# demeter_v23.net
KiCad netlist of a schematic drawn in EAGLE
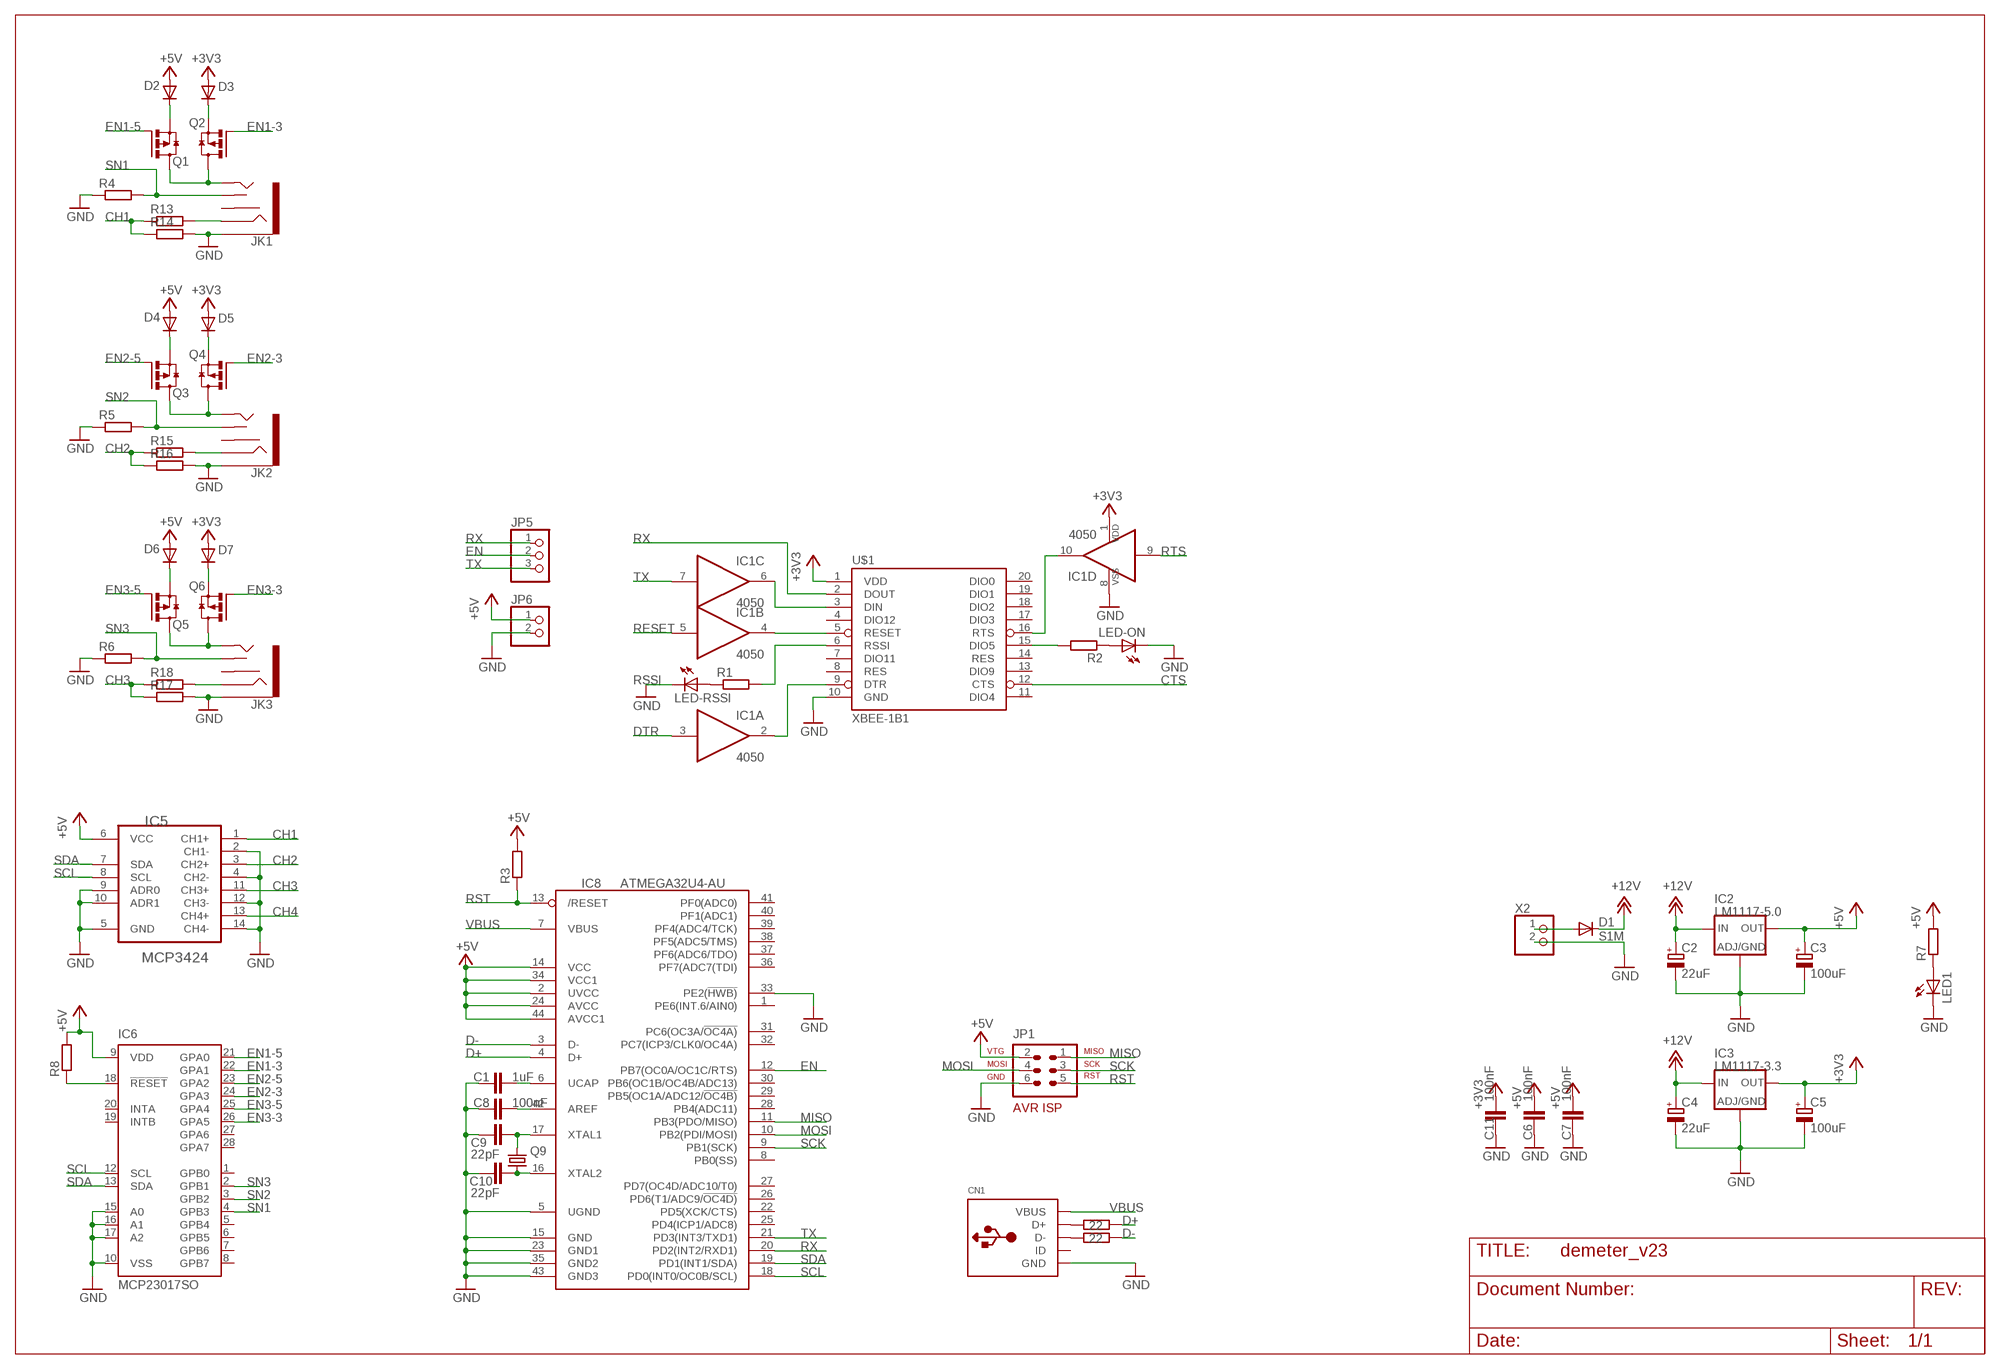
[diagram p0: schematic, sheet 1]

(export (version "E")
  (design (tool "Eeschema 10.0.6"))
  (components
    (comp (ref "C1")
      (value "1uF")
      (footprint "eagle-import:C0805K")
      (libsource (lib "eagle-import") (part "C-EUC0805K"))
    )
    (comp (ref "C2")
      (value "22uF")
      (footprint "eagle-import:PANASONIC_D")
      (libsource (lib "eagle-import") (part "CPOL-EUPD"))
    )
    (comp (ref "C3")
      (value "100uF")
      (footprint "eagle-import:PANASONIC_D")
      (libsource (lib "eagle-import") (part "CPOL-EUPD"))
    )
    (comp (ref "C4")
      (value "22uF")
      (footprint "eagle-import:PANASONIC_D")
      (libsource (lib "eagle-import") (part "CPOL-EUPD"))
    )
    (comp (ref "C5")
      (value "100uF")
      (footprint "eagle-import:PANASONIC_D")
      (libsource (lib "eagle-import") (part "CPOL-EUPD"))
    )
    (comp (ref "C6")
      (value "100nF")
      (footprint "eagle-import:C0805K")
      (libsource (lib "eagle-import") (part "C-EUC0805K"))
    )
    (comp (ref "C7")
      (value "100nF")
      (footprint "eagle-import:C0805K")
      (libsource (lib "eagle-import") (part "C-EUC0805K"))
    )
    (comp (ref "C8")
      (value "100nF")
      (footprint "eagle-import:C0805K")
      (libsource (lib "eagle-import") (part "C-EUC0805K"))
    )
    (comp (ref "C9")
      (value "22pF")
      (footprint "eagle-import:C0805K")
      (libsource (lib "eagle-import") (part "C-EUC0805K"))
    )
    (comp (ref "C10")
      (value "22pF")
      (footprint "eagle-import:C0805K")
      (libsource (lib "eagle-import") (part "C-EUC0805K"))
    )
    (comp (ref "C11")
      (value "100nF")
      (footprint "eagle-import:C0805K")
      (libsource (lib "eagle-import") (part "C-EUC0805K"))
    )
    (comp (ref "CN1")
      (value "USBMINIB")
      (footprint "eagle-import:USB-MINIB")
      (libsource (lib "eagle-import") (part "USBMINIB"))
    )
    (comp (ref "D1")
      (value "S1M")
      (footprint "eagle-import:DO-214AC")
      (libsource (lib "eagle-import") (part "S1M"))
    )
    (comp (ref "D2")
      (value "MBR0520")
      (footprint "eagle-import:SOD123")
      (libsource (lib "eagle-import") (part "MBR0520"))
    )
    (comp (ref "D3")
      (value "MBR0520")
      (footprint "eagle-import:SOD123")
      (libsource (lib "eagle-import") (part "MBR0520"))
    )
    (comp (ref "D4")
      (value "MBR0520")
      (footprint "eagle-import:SOD123")
      (libsource (lib "eagle-import") (part "MBR0520"))
    )
    (comp (ref "D5")
      (value "MBR0520")
      (footprint "eagle-import:SOD123")
      (libsource (lib "eagle-import") (part "MBR0520"))
    )
    (comp (ref "D6")
      (value "MBR0520")
      (footprint "eagle-import:SOD123")
      (libsource (lib "eagle-import") (part "MBR0520"))
    )
    (comp (ref "D7")
      (value "MBR0520")
      (footprint "eagle-import:SOD123")
      (libsource (lib "eagle-import") (part "MBR0520"))
    )
    (comp (ref "IC1")
      (value "4050")
      (footprint "eagle-import:SO16")
      (libsource (lib "eagle-import") (part "4050D"))
    )
    (comp (ref "IC2")
      (value "LM1117-5.0")
      (footprint "eagle-import:DPACK")
      (libsource (lib "eagle-import") (part "LM1117DT"))
    )
    (comp (ref "IC3")
      (value "LM1117-3.3")
      (footprint "eagle-import:DPACK")
      (libsource (lib "eagle-import") (part "LM1117DT"))
    )
    (comp (ref "IC5")
      (value "MCP3424")
      (footprint "eagle-import:SO14")
      (fields (field (name "MPN") "MCP3424-E/SL"))
      (libsource (lib "eagle-import") (part "MCP3424"))
    )
    (comp (ref "IC6")
      (value "MCP23017SO")
      (footprint "eagle-import:SO28W")
      (fields (field (name "MF") "MICROCHIP") (field (name "MPN") "MCP23017-E/SO"))
      (libsource (lib "eagle-import") (part "MCP23017SO"))
    )
    (comp (ref "IC8")
      (value "ATMEGA32U4-AU")
      (footprint "eagle-import:TQFP44")
      (libsource (lib "eagle-import") (part "ATMEGA32U4-AU"))
    )
    (comp (ref "JK1")
      (value "AUDIO-JACK2PTH")
      (footprint "eagle-import:AUDIO-JACK")
      (libsource (lib "eagle-import") (part "AUDIO-JACK2PTH"))
    )
    (comp (ref "JK2")
      (value "AUDIO-JACK2PTH")
      (footprint "eagle-import:AUDIO-JACK")
      (libsource (lib "eagle-import") (part "AUDIO-JACK2PTH"))
    )
    (comp (ref "JK3")
      (value "AUDIO-JACK2PTH")
      (footprint "eagle-import:AUDIO-JACK")
      (libsource (lib "eagle-import") (part "AUDIO-JACK2PTH"))
    )
    (comp (ref "JP1")
      (value "AVR-ISP-6")
      (footprint "eagle-import:AVR-ISP-6")
      (libsource (lib "eagle-import") (part "AVR-ISP-6"))
    )
    (comp (ref "JP5")
      (value "PINHD-1X3180")
      (footprint "eagle-import:1X03")
      (libsource (lib "eagle-import") (part "PINHD-1X3180"))
    )
    (comp (ref "JP6")
      (value "PINHD-1X2")
      (footprint "eagle-import:1X02")
      (libsource (lib "eagle-import") (part "PINHD-1X2"))
    )
    (comp (ref "LED-ON")
      (value "LED0805")
      (footprint "eagle-import:CHIP-LED0805")
      (libsource (lib "eagle-import") (part "LED0805"))
    )
    (comp (ref "LED-RSSI")
      (value "LED0805")
      (footprint "eagle-import:CHIP-LED0805")
      (libsource (lib "eagle-import") (part "LED0805"))
    )
    (comp (ref "LED1")
      (value "LED0805")
      (footprint "eagle-import:CHIP-LED0805")
      (libsource (lib "eagle-import") (part "LED0805"))
    )
    (comp (ref "Q1")
      (value "IRLML6402")
      (footprint "eagle-import:SOT23")
      (libsource (lib "eagle-import") (part "IRLML6402"))
    )
    (comp (ref "Q2")
      (value "IRLML6402")
      (footprint "eagle-import:SOT23")
      (libsource (lib "eagle-import") (part "IRLML6402"))
    )
    (comp (ref "Q3")
      (value "IRLML6402")
      (footprint "eagle-import:SOT23")
      (libsource (lib "eagle-import") (part "IRLML6402"))
    )
    (comp (ref "Q4")
      (value "IRLML6402")
      (footprint "eagle-import:SOT23")
      (libsource (lib "eagle-import") (part "IRLML6402"))
    )
    (comp (ref "Q5")
      (value "IRLML6402")
      (footprint "eagle-import:SOT23")
      (libsource (lib "eagle-import") (part "IRLML6402"))
    )
    (comp (ref "Q6")
      (value "IRLML6402")
      (footprint "eagle-import:SOT23")
      (libsource (lib "eagle-import") (part "IRLML6402"))
    )
    (comp (ref "Q9")
      (value "CRYSTALHC49UP")
      (footprint "eagle-import:HC49UP")
      (libsource (lib "eagle-import") (part "CRYSTALHC49UP"))
    )
    (comp (ref "R1")
      (value "R-EU_R0805")
      (footprint "eagle-import:R0805")
      (libsource (lib "eagle-import") (part "R-EU_R0805"))
    )
    (comp (ref "R2")
      (value "R-EU_R0805")
      (footprint "eagle-import:R0805")
      (libsource (lib "eagle-import") (part "R-EU_R0805"))
    )
    (comp (ref "R3")
      (value "R-EU_R0805")
      (footprint "eagle-import:R0805")
      (libsource (lib "eagle-import") (part "R-EU_R0805"))
    )
    (comp (ref "R4")
      (value "R-EU_R0805")
      (footprint "eagle-import:R0805")
      (libsource (lib "eagle-import") (part "R-EU_R0805"))
    )
    (comp (ref "R5")
      (value "R-EU_R0805")
      (footprint "eagle-import:R0805")
      (libsource (lib "eagle-import") (part "R-EU_R0805"))
    )
    (comp (ref "R6")
      (value "R-EU_R0805")
      (footprint "eagle-import:R0805")
      (libsource (lib "eagle-import") (part "R-EU_R0805"))
    )
    (comp (ref "R7")
      (value "R-EU_R0805")
      (footprint "eagle-import:R0805")
      (libsource (lib "eagle-import") (part "R-EU_R0805"))
    )
    (comp (ref "R8")
      (value "R-EU_R0805")
      (footprint "eagle-import:R0805")
      (libsource (lib "eagle-import") (part "R-EU_R0805"))
    )
    (comp (ref "R9")
      (value "22")
      (footprint "eagle-import:R0805")
      (libsource (lib "eagle-import") (part "R-EU_R0805"))
    )
    (comp (ref "R10")
      (value "22")
      (footprint "eagle-import:R0805")
      (libsource (lib "eagle-import") (part "R-EU_R0805"))
    )
    (comp (ref "R13")
      (value "R-EU_R0805")
      (footprint "eagle-import:R0805")
      (libsource (lib "eagle-import") (part "R-EU_R0805"))
    )
    (comp (ref "R14")
      (value "R-EU_R0805")
      (footprint "eagle-import:R0805")
      (libsource (lib "eagle-import") (part "R-EU_R0805"))
    )
    (comp (ref "R15")
      (value "R-EU_R0805")
      (footprint "eagle-import:R0805")
      (libsource (lib "eagle-import") (part "R-EU_R0805"))
    )
    (comp (ref "R16")
      (value "R-EU_R0805")
      (footprint "eagle-import:R0805")
      (libsource (lib "eagle-import") (part "R-EU_R0805"))
    )
    (comp (ref "R17")
      (value "R-EU_R0805")
      (footprint "eagle-import:R0805")
      (libsource (lib "eagle-import") (part "R-EU_R0805"))
    )
    (comp (ref "R18")
      (value "R-EU_R0805")
      (footprint "eagle-import:R0805")
      (libsource (lib "eagle-import") (part "R-EU_R0805"))
    )
    (comp (ref "U$1")
      (value "XBEE-1B1")
      (footprint "eagle-import:XBEE-1")
      (libsource (lib "eagle-import") (part "XBEE-1B1"))
    )
    (comp (ref "X2")
      (value "W237-102")
      (footprint "eagle-import:W237-102")
      (libsource (lib "eagle-import") (part "W237-102"))
    )
  )
  (nets
    (net (code "1") (name "+3V3") (class "Default")
      (node (ref "C11") (pin "1") (pinfunction "1_1") (pintype "passive"))
      (node (ref "C5") (pin "+") (pinfunction "+_+") (pintype "passive"))
      (node (ref "D3") (pin "A") (pinfunction "A_A") (pintype "passive"))
      (node (ref "D5") (pin "A") (pinfunction "A_A") (pintype "passive"))
      (node (ref "D7") (pin "A") (pinfunction "A_A") (pintype "passive"))
      (node (ref "IC1") (pin "1") (pinfunction "VDD_1") (pintype "power_in"))
      (node (ref "IC3") (pin "4") (pinfunction "OUT_4") (pintype "passive"))
      (node (ref "U$1") (pin "1") (pinfunction "VDD_1") (pintype "power_in"))
    )
    (net (code "2") (name "+5V") (class "Default")
      (node (ref "C3") (pin "+") (pinfunction "+_+") (pintype "passive"))
      (node (ref "C6") (pin "1") (pinfunction "1_1") (pintype "passive"))
      (node (ref "C7") (pin "1") (pinfunction "1_1") (pintype "passive"))
      (node (ref "D2") (pin "A") (pinfunction "A_A") (pintype "passive"))
      (node (ref "D4") (pin "A") (pinfunction "A_A") (pintype "passive"))
      (node (ref "D6") (pin "A") (pinfunction "A_A") (pintype "passive"))
      (node (ref "IC2") (pin "4") (pinfunction "OUT_4") (pintype "passive"))
      (node (ref "IC5") (pin "6") (pinfunction "VCC_6") (pintype "power_in"))
      (node (ref "IC6") (pin "9") (pinfunction "VDD_9") (pintype "power_in"))
      (node (ref "IC8") (pin "14") (pinfunction "VCC_14") (pintype "bidirectional"))
      (node (ref "IC8") (pin "2") (pinfunction "UVCC_2") (pintype "bidirectional"))
      (node (ref "IC8") (pin "24") (pinfunction "AVCC_24") (pintype "bidirectional"))
      (node (ref "IC8") (pin "34") (pinfunction "VCC1_34") (pintype "bidirectional"))
      (node (ref "IC8") (pin "44") (pinfunction "AVCC1_44") (pintype "bidirectional"))
      (node (ref "JP1") (pin "2") (pinfunction "VTG_2") (pintype "passive"))
      (node (ref "JP6") (pin "1") (pinfunction "1_1") (pintype "passive"))
      (node (ref "R3") (pin "2") (pinfunction "2_2") (pintype "passive"))
      (node (ref "R7") (pin "2") (pinfunction "2_2") (pintype "passive"))
      (node (ref "R8") (pin "2") (pinfunction "2_2") (pintype "passive"))
    )
    (net (code "3") (name "+12V") (class "Default")
      (node (ref "C2") (pin "+") (pinfunction "+_+") (pintype "passive"))
      (node (ref "C4") (pin "+") (pinfunction "+_+") (pintype "passive"))
      (node (ref "D1") (pin "C") (pinfunction "C_C") (pintype "passive"))
      (node (ref "IC2") (pin "3") (pinfunction "IN_3") (pintype "input"))
      (node (ref "IC3") (pin "3") (pinfunction "IN_3") (pintype "input"))
    )
    (net (code "4") (name "/CH1") (class "Default")
      (node (ref "IC5") (pin "1") (pinfunction "CH1+_1") (pintype "input"))
      (node (ref "R13") (pin "1") (pinfunction "1_1") (pintype "passive"))
      (node (ref "R14") (pin "1") (pinfunction "1_1") (pintype "passive"))
    )
    (net (code "5") (name "/CH2") (class "Default")
      (node (ref "IC5") (pin "3") (pinfunction "CH2+_3") (pintype "input"))
      (node (ref "R15") (pin "1") (pinfunction "1_1") (pintype "passive"))
      (node (ref "R16") (pin "1") (pinfunction "1_1") (pintype "passive"))
    )
    (net (code "6") (name "/CH3") (class "Default")
      (node (ref "IC5") (pin "11") (pinfunction "CH3+_11") (pintype "input"))
      (node (ref "R17") (pin "1") (pinfunction "1_1") (pintype "passive"))
      (node (ref "R18") (pin "1") (pinfunction "1_1") (pintype "passive"))
    )
    (net (code "7") (name "/CH4") (class "Default")
      (node (ref "IC5") (pin "13") (pinfunction "CH4+_13") (pintype "input"))
    )
    (net (code "8") (name "/CTS") (class "Default")
      (node (ref "U$1") (pin "12") (pinfunction "CTS_12") (pintype "output"))
    )
    (net (code "9") (name "/D+") (class "Default")
      (node (ref "IC8") (pin "4") (pinfunction "D+_4") (pintype "bidirectional"))
      (node (ref "R9") (pin "1") (pinfunction "1_1") (pintype "passive"))
    )
    (net (code "10") (name "/D-") (class "Default")
      (node (ref "IC8") (pin "3") (pinfunction "D-_3") (pintype "bidirectional"))
      (node (ref "R10") (pin "1") (pinfunction "1_1") (pintype "passive"))
    )
    (net (code "11") (name "/DTR") (class "Default")
      (node (ref "IC1") (pin "3") (pinfunction "I_3") (pintype "input"))
    )
    (net (code "12") (name "/EN") (class "Default")
      (node (ref "IC8") (pin "12") (pinfunction "PB7(OC0A/OC1C/RTS)_12") (pintype "bidirectional"))
      (node (ref "JP5") (pin "2") (pinfunction "2_2") (pintype "passive"))
    )
    (net (code "13") (name "/EN1-3") (class "Default")
      (node (ref "IC6") (pin "22") (pinfunction "GPA1_22") (pintype "bidirectional"))
      (node (ref "Q2") (pin "1") (pinfunction "G_1") (pintype "passive"))
    )
    (net (code "14") (name "/EN1-5") (class "Default")
      (node (ref "IC6") (pin "21") (pinfunction "GPA0_21") (pintype "bidirectional"))
      (node (ref "Q1") (pin "1") (pinfunction "G_1") (pintype "passive"))
    )
    (net (code "15") (name "/EN2-3") (class "Default")
      (node (ref "IC6") (pin "24") (pinfunction "GPA3_24") (pintype "bidirectional"))
      (node (ref "Q4") (pin "1") (pinfunction "G_1") (pintype "passive"))
    )
    (net (code "16") (name "/EN2-5") (class "Default")
      (node (ref "IC6") (pin "23") (pinfunction "GPA2_23") (pintype "bidirectional"))
      (node (ref "Q3") (pin "1") (pinfunction "G_1") (pintype "passive"))
    )
    (net (code "17") (name "/EN3-3") (class "Default")
      (node (ref "IC6") (pin "26") (pinfunction "GPA5_26") (pintype "bidirectional"))
      (node (ref "Q6") (pin "1") (pinfunction "G_1") (pintype "passive"))
    )
    (net (code "18") (name "/EN3-5") (class "Default")
      (node (ref "IC6") (pin "25") (pinfunction "GPA4_25") (pintype "bidirectional"))
      (node (ref "Q5") (pin "1") (pinfunction "G_1") (pintype "passive"))
    )
    (net (code "19") (name "/MISO") (class "Default")
      (node (ref "IC8") (pin "11") (pinfunction "PB3(PDO/MISO)_11") (pintype "bidirectional"))
      (node (ref "JP1") (pin "1") (pinfunction "MISO_1") (pintype "passive"))
    )
    (net (code "20") (name "/MOSI") (class "Default")
      (node (ref "IC8") (pin "10") (pinfunction "PB2(PDI/MOSI)_10") (pintype "bidirectional"))
      (node (ref "JP1") (pin "4") (pinfunction "MOSI_4") (pintype "passive"))
    )
    (net (code "21") (name "/RESET") (class "Default")
      (node (ref "IC1") (pin "5") (pinfunction "I_5") (pintype "input"))
    )
    (net (code "22") (name "/RSSI") (class "Default")
      (node (ref "R1") (pin "2") (pinfunction "2_2") (pintype "passive"))
      (node (ref "U$1") (pin "6") (pinfunction "RSSI_6") (pintype "bidirectional"))
    )
    (net (code "23") (name "/RST") (class "Default")
      (node (ref "IC8") (pin "13") (pinfunction "/RESET_13") (pintype "bidirectional"))
      (node (ref "JP1") (pin "5") (pinfunction "RST_5") (pintype "passive"))
      (node (ref "R3") (pin "1") (pinfunction "1_1") (pintype "passive"))
    )
    (net (code "24") (name "/RTS") (class "Default")
      (node (ref "IC1") (pin "9") (pinfunction "I_9") (pintype "input"))
    )
    (net (code "25") (name "/RX") (class "Default")
      (node (ref "IC8") (pin "20") (pinfunction "PD2(INT2/RXD1)_20") (pintype "bidirectional"))
      (node (ref "JP5") (pin "1") (pinfunction "1_1") (pintype "passive"))
      (node (ref "U$1") (pin "2") (pinfunction "DOUT_2") (pintype "output"))
    )
    (net (code "26") (name "/SCK") (class "Default")
      (node (ref "IC8") (pin "9") (pinfunction "PB1(SCK)_9") (pintype "bidirectional"))
      (node (ref "JP1") (pin "3") (pinfunction "SCK_3") (pintype "passive"))
    )
    (net (code "27") (name "/SCL") (class "Default")
      (node (ref "IC5") (pin "8") (pinfunction "SCL_8") (pintype "input"))
      (node (ref "IC6") (pin "12") (pinfunction "SCL_12") (pintype "input"))
      (node (ref "IC8") (pin "18") (pinfunction "PD0(INT0/OC0B/SCL)_18") (pintype "bidirectional"))
    )
    (net (code "28") (name "/SDA") (class "Default")
      (node (ref "IC5") (pin "7") (pinfunction "SDA_7") (pintype "bidirectional"))
      (node (ref "IC6") (pin "13") (pinfunction "SDA_13") (pintype "bidirectional"))
      (node (ref "IC8") (pin "19") (pinfunction "PD1(INT1/SDA)_19") (pintype "bidirectional"))
    )
    (net (code "29") (name "/SN1") (class "Default")
      (node (ref "IC6") (pin "4") (pinfunction "GPB3_4") (pintype "bidirectional"))
      (node (ref "JK1") (pin "TSH") (pinfunction "TSH_TSH") (pintype "bidirectional"))
      (node (ref "R4") (pin "2") (pinfunction "2_2") (pintype "passive"))
    )
    (net (code "30") (name "/SN2") (class "Default")
      (node (ref "IC6") (pin "3") (pinfunction "GPB2_3") (pintype "bidirectional"))
      (node (ref "JK2") (pin "TSH") (pinfunction "TSH_TSH") (pintype "bidirectional"))
      (node (ref "R5") (pin "2") (pinfunction "2_2") (pintype "passive"))
    )
    (net (code "31") (name "/SN3") (class "Default")
      (node (ref "IC6") (pin "2") (pinfunction "GPB1_2") (pintype "bidirectional"))
      (node (ref "JK3") (pin "TSH") (pinfunction "TSH_TSH") (pintype "bidirectional"))
      (node (ref "R6") (pin "2") (pinfunction "2_2") (pintype "passive"))
    )
    (net (code "32") (name "/TX") (class "Default")
      (node (ref "IC1") (pin "7") (pinfunction "I_7") (pintype "input"))
      (node (ref "IC8") (pin "21") (pinfunction "PD3(INT3/TXD1)_21") (pintype "bidirectional"))
      (node (ref "JP5") (pin "3") (pinfunction "3_3") (pintype "passive"))
    )
    (net (code "33") (name "/VBUS") (class "Default")
      (node (ref "CN1") (pin "VBUS") (pinfunction "VBUS_VBUS") (pintype "power_in"))
      (node (ref "IC8") (pin "7") (pinfunction "VBUS_7") (pintype "bidirectional"))
    )
    (net (code "34") (name "GND") (class "Default")
      (node (ref "C1") (pin "2") (pinfunction "2_2") (pintype "passive"))
      (node (ref "C10") (pin "2") (pinfunction "2_2") (pintype "passive"))
      (node (ref "C11") (pin "2") (pinfunction "2_2") (pintype "passive"))
      (node (ref "C2") (pin "-") (pinfunction "-_-") (pintype "passive"))
      (node (ref "C3") (pin "-") (pinfunction "-_-") (pintype "passive"))
      (node (ref "C4") (pin "-") (pinfunction "-_-") (pintype "passive"))
      (node (ref "C5") (pin "-") (pinfunction "-_-") (pintype "passive"))
      (node (ref "C6") (pin "2") (pinfunction "2_2") (pintype "passive"))
      (node (ref "C7") (pin "2") (pinfunction "2_2") (pintype "passive"))
      (node (ref "C8") (pin "2") (pinfunction "2_2") (pintype "passive"))
      (node (ref "C9") (pin "2") (pinfunction "2_2") (pintype "passive"))
      (node (ref "CN1") (pin "GND") (pinfunction "GND_GND") (pintype "power_in"))
      (node (ref "IC1") (pin "8") (pinfunction "VSS_8") (pintype "power_in"))
      (node (ref "IC2") (pin "1") (pinfunction "ADJ_1") (pintype "input"))
      (node (ref "IC3") (pin "1") (pinfunction "ADJ_1") (pintype "input"))
      (node (ref "IC5") (pin "10") (pinfunction "ADR1_10") (pintype "input"))
      (node (ref "IC5") (pin "12") (pinfunction "CH3-_12") (pintype "input"))
      (node (ref "IC5") (pin "14") (pinfunction "CH4-_14") (pintype "input"))
      (node (ref "IC5") (pin "2") (pinfunction "CH1-_2") (pintype "input"))
      (node (ref "IC5") (pin "4") (pinfunction "CH2-_4") (pintype "input"))
      (node (ref "IC5") (pin "5") (pinfunction "GND_5") (pintype "power_in"))
      (node (ref "IC5") (pin "9") (pinfunction "ADR0_9") (pintype "input"))
      (node (ref "IC6") (pin "10") (pinfunction "VSS_10") (pintype "power_in"))
      (node (ref "IC6") (pin "15") (pinfunction "A0_15") (pintype "input"))
      (node (ref "IC6") (pin "16") (pinfunction "A1_16") (pintype "input"))
      (node (ref "IC6") (pin "17") (pinfunction "A2_17") (pintype "input"))
      (node (ref "IC8") (pin "15") (pinfunction "GND_15") (pintype "bidirectional"))
      (node (ref "IC8") (pin "23") (pinfunction "GND1_23") (pintype "bidirectional"))
      (node (ref "IC8") (pin "33") (pinfunction "PE2(~{HWB})_33") (pintype "bidirectional"))
      (node (ref "IC8") (pin "35") (pinfunction "GND2_35") (pintype "bidirectional"))
      (node (ref "IC8") (pin "43") (pinfunction "GND3_43") (pintype "bidirectional"))
      (node (ref "IC8") (pin "5") (pinfunction "UGND_5") (pintype "bidirectional"))
      (node (ref "JK1") (pin "SLEEVE") (pinfunction "SLEEVE_SLEEVE") (pintype "bidirectional"))
      (node (ref "JK2") (pin "SLEEVE") (pinfunction "SLEEVE_SLEEVE") (pintype "bidirectional"))
      (node (ref "JK3") (pin "SLEEVE") (pinfunction "SLEEVE_SLEEVE") (pintype "bidirectional"))
      (node (ref "JP1") (pin "6") (pinfunction "GND_6") (pintype "passive"))
      (node (ref "JP6") (pin "2") (pinfunction "2_2") (pintype "passive"))
      (node (ref "LED-ON") (pin "C") (pinfunction "C_C") (pintype "passive"))
      (node (ref "LED-RSSI") (pin "C") (pinfunction "C_C") (pintype "passive"))
      (node (ref "LED1") (pin "C") (pinfunction "C_C") (pintype "passive"))
      (node (ref "R14") (pin "2") (pinfunction "2_2") (pintype "passive"))
      (node (ref "R16") (pin "2") (pinfunction "2_2") (pintype "passive"))
      (node (ref "R17") (pin "2") (pinfunction "2_2") (pintype "passive"))
      (node (ref "R4") (pin "1") (pinfunction "1_1") (pintype "passive"))
      (node (ref "R5") (pin "1") (pinfunction "1_1") (pintype "passive"))
      (node (ref "R6") (pin "1") (pinfunction "1_1") (pintype "passive"))
      (node (ref "U$1") (pin "10") (pinfunction "GND_10") (pintype "power_in"))
      (node (ref "X2") (pin "2") (pinfunction "2_2") (pintype "passive"))
    )
    (net (code "35") (name "Net-(CN1-PadD+)") (class "Default")
      (node (ref "CN1") (pin "D+") (pinfunction "D+_D+") (pintype "bidirectional"))
      (node (ref "R9") (pin "2") (pinfunction "2_2") (pintype "passive"))
    )
    (net (code "36") (name "Net-(CN1-PadD-)") (class "Default")
      (node (ref "CN1") (pin "D-") (pinfunction "D-_D-") (pintype "bidirectional"))
      (node (ref "R10") (pin "2") (pinfunction "2_2") (pintype "passive"))
    )
    (net (code "37") (name "Net-(D1-PadA)") (class "Default")
      (node (ref "D1") (pin "A") (pinfunction "A_A") (pintype "passive"))
      (node (ref "X2") (pin "1") (pinfunction "1_1") (pintype "passive"))
    )
    (net (code "38") (name "Net-(IC1A-O)") (class "Default")
      (node (ref "IC1") (pin "2") (pinfunction "O_2") (pintype "output"))
      (node (ref "U$1") (pin "9") (pinfunction "DTR_9") (pintype "bidirectional"))
    )
    (net (code "39") (name "Net-(IC1B-O)") (class "Default")
      (node (ref "IC1") (pin "4") (pinfunction "O_4") (pintype "output"))
      (node (ref "U$1") (pin "5") (pinfunction "RESET_5") (pintype "input"))
    )
    (net (code "40") (name "Net-(IC1C-O)") (class "Default")
      (node (ref "IC1") (pin "6") (pinfunction "O_6") (pintype "output"))
      (node (ref "U$1") (pin "3") (pinfunction "DIN_3") (pintype "input"))
    )
    (net (code "41") (name "Net-(IC1D-O)") (class "Default")
      (node (ref "IC1") (pin "10") (pinfunction "O_10") (pintype "output"))
      (node (ref "U$1") (pin "16") (pinfunction "RTS_16") (pintype "input"))
    )
    (net (code "42") (name "Net-(IC6-~{RESET})") (class "Default")
      (node (ref "IC6") (pin "18") (pinfunction "~{RESET}_18") (pintype "input"))
      (node (ref "R8") (pin "1") (pinfunction "1_1") (pintype "passive"))
    )
    (net (code "43") (name "Net-(IC8-AREF)") (class "Default")
      (node (ref "C8") (pin "1") (pinfunction "1_1") (pintype "passive"))
      (node (ref "IC8") (pin "42") (pinfunction "AREF_42") (pintype "bidirectional"))
    )
    (net (code "44") (name "Net-(IC8-UCAP)") (class "Default")
      (node (ref "C1") (pin "1") (pinfunction "1_1") (pintype "passive"))
      (node (ref "IC8") (pin "6") (pinfunction "UCAP_6") (pintype "bidirectional"))
    )
    (net (code "45") (name "Net-(IC8-XTAL1)") (class "Default")
      (node (ref "C9") (pin "1") (pinfunction "1_1") (pintype "passive"))
      (node (ref "IC8") (pin "17") (pinfunction "XTAL1_17") (pintype "bidirectional"))
      (node (ref "Q9") (pin "2") (pinfunction "2_2") (pintype "passive"))
    )
    (net (code "46") (name "Net-(IC8-XTAL2)") (class "Default")
      (node (ref "C10") (pin "1") (pinfunction "1_1") (pintype "passive"))
      (node (ref "IC8") (pin "16") (pinfunction "XTAL2_16") (pintype "bidirectional"))
      (node (ref "Q9") (pin "1") (pinfunction "1_1") (pintype "passive"))
    )
    (net (code "47") (name "Net-(JK1-PadRING)") (class "Default")
      (node (ref "JK1") (pin "RING") (pinfunction "RING_RING") (pintype "bidirectional"))
      (node (ref "R13") (pin "2") (pinfunction "2_2") (pintype "passive"))
    )
    (net (code "48") (name "Net-(JK2-PadRING)") (class "Default")
      (node (ref "JK2") (pin "RING") (pinfunction "RING_RING") (pintype "bidirectional"))
      (node (ref "R15") (pin "2") (pinfunction "2_2") (pintype "passive"))
    )
    (net (code "49") (name "Net-(JK3-PadRING)") (class "Default")
      (node (ref "JK3") (pin "RING") (pinfunction "RING_RING") (pintype "bidirectional"))
      (node (ref "R18") (pin "2") (pinfunction "2_2") (pintype "passive"))
    )
    (net (code "50") (name "Net-(LED-ON-PadA)") (class "Default")
      (node (ref "LED-ON") (pin "A") (pinfunction "A_A") (pintype "passive"))
      (node (ref "R2") (pin "1") (pinfunction "1_1") (pintype "passive"))
    )
    (net (code "51") (name "Net-(LED-RSSI-PadA)") (class "Default")
      (node (ref "LED-RSSI") (pin "A") (pinfunction "A_A") (pintype "passive"))
      (node (ref "R1") (pin "1") (pinfunction "1_1") (pintype "passive"))
    )
    (net (code "52") (name "Net-(LED1-PadA)") (class "Default")
      (node (ref "LED1") (pin "A") (pinfunction "A_A") (pintype "passive"))
      (node (ref "R7") (pin "1") (pinfunction "1_1") (pintype "passive"))
    )
    (net (code "53") (name "Net-(Q1-D)") (class "Default")
      (node (ref "JK1") (pin "TIP") (pinfunction "TIP_TIP") (pintype "bidirectional"))
      (node (ref "Q1") (pin "3") (pinfunction "D_3") (pintype "passive"))
      (node (ref "Q2") (pin "3") (pinfunction "D_3") (pintype "passive"))
    )
    (net (code "54") (name "Net-(Q1-S)") (class "Default")
      (node (ref "D2") (pin "C") (pinfunction "C_C") (pintype "passive"))
      (node (ref "Q1") (pin "2") (pinfunction "S_2") (pintype "passive"))
    )
    (net (code "55") (name "Net-(Q2-S)") (class "Default")
      (node (ref "D3") (pin "C") (pinfunction "C_C") (pintype "passive"))
      (node (ref "Q2") (pin "2") (pinfunction "S_2") (pintype "passive"))
    )
    (net (code "56") (name "Net-(Q3-D)") (class "Default")
      (node (ref "JK2") (pin "TIP") (pinfunction "TIP_TIP") (pintype "bidirectional"))
      (node (ref "Q3") (pin "3") (pinfunction "D_3") (pintype "passive"))
      (node (ref "Q4") (pin "3") (pinfunction "D_3") (pintype "passive"))
    )
    (net (code "57") (name "Net-(Q3-S)") (class "Default")
      (node (ref "D4") (pin "C") (pinfunction "C_C") (pintype "passive"))
      (node (ref "Q3") (pin "2") (pinfunction "S_2") (pintype "passive"))
    )
    (net (code "58") (name "Net-(Q4-S)") (class "Default")
      (node (ref "D5") (pin "C") (pinfunction "C_C") (pintype "passive"))
      (node (ref "Q4") (pin "2") (pinfunction "S_2") (pintype "passive"))
    )
    (net (code "59") (name "Net-(Q5-D)") (class "Default")
      (node (ref "JK3") (pin "TIP") (pinfunction "TIP_TIP") (pintype "bidirectional"))
      (node (ref "Q5") (pin "3") (pinfunction "D_3") (pintype "passive"))
      (node (ref "Q6") (pin "3") (pinfunction "D_3") (pintype "passive"))
    )
    (net (code "60") (name "Net-(Q5-S)") (class "Default")
      (node (ref "D6") (pin "C") (pinfunction "C_C") (pintype "passive"))
      (node (ref "Q5") (pin "2") (pinfunction "S_2") (pintype "passive"))
    )
    (net (code "61") (name "Net-(Q6-S)") (class "Default")
      (node (ref "D7") (pin "C") (pinfunction "C_C") (pintype "passive"))
      (node (ref "Q6") (pin "2") (pinfunction "S_2") (pintype "passive"))
    )
    (net (code "62") (name "Net-(U$1-DIO5)") (class "Default")
      (node (ref "R2") (pin "2") (pinfunction "2_2") (pintype "passive"))
      (node (ref "U$1") (pin "15") (pinfunction "DIO5_15") (pintype "bidirectional"))
    )
    (net (code "63") (name "unconnected-(CN1-PadID)") (class "Default")
      (node (ref "CN1") (pin "ID") (pinfunction "ID_ID") (pintype "bidirectional"))
    )
    (net (code "64") (name "unconnected-(IC6-GPA6-Pad27)") (class "Default")
      (node (ref "IC6") (pin "27") (pinfunction "GPA6_27") (pintype "bidirectional"))
    )
    (net (code "65") (name "unconnected-(IC6-GPA7-Pad28)") (class "Default")
      (node (ref "IC6") (pin "28") (pinfunction "GPA7_28") (pintype "bidirectional"))
    )
    (net (code "66") (name "unconnected-(IC6-GPB0-Pad1)") (class "Default")
      (node (ref "IC6") (pin "1") (pinfunction "GPB0_1") (pintype "bidirectional"))
    )
    (net (code "67") (name "unconnected-(IC6-GPB4-Pad5)") (class "Default")
      (node (ref "IC6") (pin "5") (pinfunction "GPB4_5") (pintype "bidirectional"))
    )
    (net (code "68") (name "unconnected-(IC6-GPB5-Pad6)") (class "Default")
      (node (ref "IC6") (pin "6") (pinfunction "GPB5_6") (pintype "bidirectional"))
    )
    (net (code "69") (name "unconnected-(IC6-GPB6-Pad7)") (class "Default")
      (node (ref "IC6") (pin "7") (pinfunction "GPB6_7") (pintype "bidirectional"))
    )
    (net (code "70") (name "unconnected-(IC6-GPB7-Pad8)") (class "Default")
      (node (ref "IC6") (pin "8") (pinfunction "GPB7_8") (pintype "bidirectional"))
    )
    (net (code "71") (name "unconnected-(IC6-INTA-Pad20)") (class "Default")
      (node (ref "IC6") (pin "20") (pinfunction "INTA_20") (pintype "output"))
    )
    (net (code "72") (name "unconnected-(IC6-INTB-Pad19)") (class "Default")
      (node (ref "IC6") (pin "19") (pinfunction "INTB_19") (pintype "output"))
    )
    (net (code "73") (name "unconnected-(IC8-PB0(SS)-Pad8)") (class "Default")
      (node (ref "IC8") (pin "8") (pinfunction "PB0(SS)_8") (pintype "bidirectional"))
    )
    (net (code "74") (name "unconnected-(IC8-PB4(ADC11)-Pad28)") (class "Default")
      (node (ref "IC8") (pin "28") (pinfunction "PB4(ADC11)_28") (pintype "bidirectional"))
    )
    (net (code "75") (name "unconnected-(IC8-PB5(OC1A{slash}ADC12{slash}~{OC4B})-Pad29)") (class "Default")
      (node (ref "IC8") (pin "29") (pinfunction "PB5(OC1A/ADC12/~{OC4B})_29") (pintype "bidirectional"))
    )
    (net (code "76") (name "unconnected-(IC8-PB6(OC1B{slash}OC4B{slash}ADC13)-Pad30)") (class "Default")
      (node (ref "IC8") (pin "30") (pinfunction "PB6(OC1B/OC4B/ADC13)_30") (pintype "bidirectional"))
    )
    (net (code "77") (name "unconnected-(IC8-PC6(OC3A{slash}~{OC4A})-Pad31)") (class "Default")
      (node (ref "IC8") (pin "31") (pinfunction "PC6(OC3A/~{OC4A})_31") (pintype "bidirectional"))
    )
    (net (code "78") (name "unconnected-(IC8-PC7(ICP3{slash}CLK0{slash}OC4A)-Pad32)") (class "Default")
      (node (ref "IC8") (pin "32") (pinfunction "PC7(ICP3/CLK0/OC4A)_32") (pintype "bidirectional"))
    )
    (net (code "79") (name "unconnected-(IC8-PD4(ICP1{slash}ADC8)-Pad25)") (class "Default")
      (node (ref "IC8") (pin "25") (pinfunction "PD4(ICP1/ADC8)_25") (pintype "bidirectional"))
    )
    (net (code "80") (name "unconnected-(IC8-PD5(XCK{slash}CTS)-Pad22)") (class "Default")
      (node (ref "IC8") (pin "22") (pinfunction "PD5(XCK/CTS)_22") (pintype "bidirectional"))
    )
    (net (code "81") (name "unconnected-(IC8-PD6(T1{slash}ADC9{slash}~{OC4D})-Pad26)") (class "Default")
      (node (ref "IC8") (pin "26") (pinfunction "PD6(T1/ADC9/~{OC4D})_26") (pintype "bidirectional"))
    )
    (net (code "82") (name "unconnected-(IC8-PD7(OC4D{slash}ADC10{slash}T0)-Pad27)") (class "Default")
      (node (ref "IC8") (pin "27") (pinfunction "PD7(OC4D/ADC10/T0)_27") (pintype "bidirectional"))
    )
    (net (code "83") (name "unconnected-(IC8-PE6(INT.6{slash}AIN0)-Pad1)") (class "Default")
      (node (ref "IC8") (pin "1") (pinfunction "PE6(INT.6/AIN0)_1") (pintype "bidirectional"))
    )
    (net (code "84") (name "unconnected-(IC8-PF0(ADC0)-Pad41)") (class "Default")
      (node (ref "IC8") (pin "41") (pinfunction "PF0(ADC0)_41") (pintype "bidirectional"))
    )
    (net (code "85") (name "unconnected-(IC8-PF1(ADC1)-Pad40)") (class "Default")
      (node (ref "IC8") (pin "40") (pinfunction "PF1(ADC1)_40") (pintype "bidirectional"))
    )
    (net (code "86") (name "unconnected-(IC8-PF4(ADC4{slash}TCK)-Pad39)") (class "Default")
      (node (ref "IC8") (pin "39") (pinfunction "PF4(ADC4/TCK)_39") (pintype "bidirectional"))
    )
    (net (code "87") (name "unconnected-(IC8-PF5(ADC5{slash}TMS)-Pad38)") (class "Default")
      (node (ref "IC8") (pin "38") (pinfunction "PF5(ADC5/TMS)_38") (pintype "bidirectional"))
    )
    (net (code "88") (name "unconnected-(IC8-PF6(ADC6{slash}TDO)-Pad37)") (class "Default")
      (node (ref "IC8") (pin "37") (pinfunction "PF6(ADC6/TDO)_37") (pintype "bidirectional"))
    )
    (net (code "89") (name "unconnected-(IC8-PF7(ADC7(TDI)-Pad36)") (class "Default")
      (node (ref "IC8") (pin "36") (pinfunction "PF7(ADC7(TDI)_36") (pintype "bidirectional"))
    )
    (net (code "90") (name "unconnected-(JK1-PadRSH)") (class "Default")
      (node (ref "JK1") (pin "RSH") (pinfunction "RSH_RSH") (pintype "bidirectional"))
    )
    (net (code "91") (name "unconnected-(JK2-PadRSH)") (class "Default")
      (node (ref "JK2") (pin "RSH") (pinfunction "RSH_RSH") (pintype "bidirectional"))
    )
    (net (code "92") (name "unconnected-(JK3-PadRSH)") (class "Default")
      (node (ref "JK3") (pin "RSH") (pinfunction "RSH_RSH") (pintype "bidirectional"))
    )
    (net (code "93") (name "unconnected-(U$1-DIO0-Pad20)") (class "Default")
      (node (ref "U$1") (pin "20") (pinfunction "DIO0_20") (pintype "bidirectional"))
    )
    (net (code "94") (name "unconnected-(U$1-DIO1-Pad19)") (class "Default")
      (node (ref "U$1") (pin "19") (pinfunction "DIO1_19") (pintype "bidirectional"))
    )
    (net (code "95") (name "unconnected-(U$1-DIO2-Pad18)") (class "Default")
      (node (ref "U$1") (pin "18") (pinfunction "DIO2_18") (pintype "bidirectional"))
    )
    (net (code "96") (name "unconnected-(U$1-DIO3-Pad17)") (class "Default")
      (node (ref "U$1") (pin "17") (pinfunction "DIO3_17") (pintype "bidirectional"))
    )
    (net (code "97") (name "unconnected-(U$1-DIO4-Pad11)") (class "Default")
      (node (ref "U$1") (pin "11") (pinfunction "DIO4_11") (pintype "bidirectional"))
    )
    (net (code "98") (name "unconnected-(U$1-DIO9-Pad13)") (class "Default")
      (node (ref "U$1") (pin "13") (pinfunction "DIO9_13") (pintype "bidirectional"))
    )
    (net (code "99") (name "unconnected-(U$1-DIO11-Pad7)") (class "Default")
      (node (ref "U$1") (pin "7") (pinfunction "DIO11_7") (pintype "bidirectional"))
    )
    (net (code "100") (name "unconnected-(U$1-DIO12-Pad4)") (class "Default")
      (node (ref "U$1") (pin "4") (pinfunction "DIO12_4") (pintype "bidirectional"))
    )
    (net (code "101") (name "unconnected-(U$1-RES-Pad8)") (class "Default")
      (node (ref "U$1") (pin "8") (pinfunction "RES_8") (pintype "bidirectional"))
    )
    (net (code "102") (name "unconnected-(U$1-RES-Pad14)") (class "Default")
      (node (ref "U$1") (pin "14") (pinfunction "RES_14") (pintype "bidirectional"))
    )
  )
)
